# IMU.net
KiCad netlist of a schematic drawn in Altium Designer
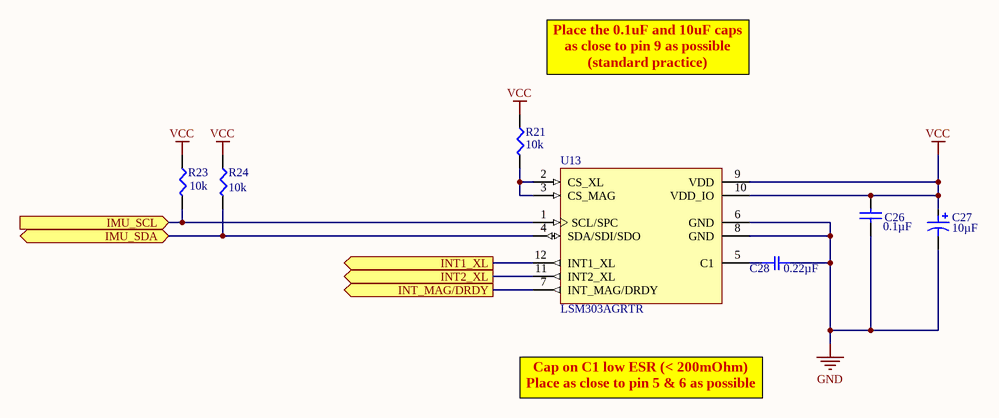
[diagram p0: IMU.SchDoc]

(export (version "E")
  (design (tool "Eeschema 10.0.6"))
  (components
    (comp (ref "C26")
      (value "CL10B104KO8NFNC")
      (footprint "C0603N")
      (fields
        (field (name "HOUSEPART") "NO")
        (field (name "TOLERANCE") "±10%")
        (field (name "VOLTAGE") "16V")
        (field (name "CAPACITANCE") "0.1µF")
      )
      (libsource (lib "MF_Passives") (part "CAPACITOR_NP"))
    )
    (comp (ref "C27")
      (value "10µF")
      (footprint "2917")
      (description "10µF 12.5V Aluminum Polymer Capacitor 2917 (7343 Metric) 60 mOhm 1000 Hrs @ 105°C")
      (fields (field (name "HOUSEPART") "NO") (field (name "MPN") "EEF-CD1B100R"))
      (libsource (lib "Passives") (part "CAPACITOR_P"))
    )
    (comp (ref "C28")
      (value "0.22µF")
      (footprint "SMD-0603C")
      (description "CAP CER 0.22UF 25V X7R 0603")
      (fields
        (field (name "DIGI-KEY PART NUMBER") "490-8017-1-ND")
        (field (name "PART NUMBER") "GCM188R71E224KA55J")
      )
      (libsource (lib "capacitor_murata_0603") (part "GCM188R71E224KA55J"))
    )
    (comp (ref "R21")
      (value "10k")
      (footprint "SMD-0603-RES")
      (description "RES SMD 10K OHM 1% 1/10W 0603")
      (fields
        (field (name "PART NUMBER") "ERJ-3EKF1002V")
        (field (name "DIGI-KEY PART NUMBER") "P10.0KHCT-ND")
      )
      (libsource (lib "Panasonic_ERJ_0603") (part "ERJ-3EKF1002V"))
    )
    (comp (ref "R23")
      (value "10k")
      (footprint "SMD-0603-RES")
      (description "RES SMD 10K OHM 1% 1/10W 0603")
      (fields
        (field (name "PART NUMBER") "ERJ-3EKF1002V")
        (field (name "DIGI-KEY PART NUMBER") "P10.0KHCT-ND")
      )
      (libsource (lib "Panasonic_ERJ_0603") (part "ERJ-3EKF1002V"))
    )
    (comp (ref "R24")
      (value "10k")
      (footprint "SMD-0603-RES")
      (description "RES SMD 10K OHM 1% 1/10W 0603")
      (fields
        (field (name "PART NUMBER") "ERJ-3EKF1002V")
        (field (name "DIGI-KEY PART NUMBER") "P10.0KHCT-ND")
      )
      (libsource (lib "Panasonic_ERJ_0603") (part "ERJ-3EKF1002V"))
    )
    (comp (ref "U13")
      (value "LSM303AGRTR")
      (footprint "LGA12R50P_200X200X100")
      (libsource (lib "LSM303AGRTR") (part "CMP-98f6527696964731-1"))
    )
  )
  (nets
    (net (code "1") (name "/IMU_SCL") (class "Default")
      (node (ref "R23") (pin "2") (pinfunction "2_2") (pintype "passive"))
      (node (ref "U13") (pin "1") (pinfunction "SCL/SPC_1") (pintype "input"))
    )
    (net (code "2") (name "/IMU_SDA") (class "Default")
      (node (ref "R24") (pin "2") (pinfunction "2_2") (pintype "passive"))
      (node (ref "U13") (pin "4") (pinfunction "SDA/SDI/SDO_4") (pintype "bidirectional"))
    )
    (net (code "3") (name "/INT1_XL") (class "Default")
      (node (ref "U13") (pin "12") (pinfunction "INT1_XL_12") (pintype "output"))
    )
    (net (code "4") (name "/INT2_XL") (class "Default")
      (node (ref "U13") (pin "11") (pinfunction "INT2_XL_11") (pintype "output"))
    )
    (net (code "5") (name "/INT_MAG{slash}DRDY") (class "Default")
      (node (ref "U13") (pin "7") (pinfunction "INT_MAG/DRDY_7") (pintype "output"))
    )
    (net (code "6") (name "GND") (class "Default")
      (node (ref "C26") (pin "1") (pinfunction "1_1") (pintype "passive"))
      (node (ref "C27") (pin "2") (pinfunction "2_2") (pintype "passive"))
      (node (ref "C28") (pin "2") (pinfunction "2_2") (pintype "passive"))
      (node (ref "U13") (pin "6") (pinfunction "GND_6") (pintype "power_in"))
      (node (ref "U13") (pin "8") (pinfunction "GND_8") (pintype "power_in"))
    )
    (net (code "7") (name "Net-(U13-C1)") (class "Default")
      (node (ref "C28") (pin "1") (pinfunction "1_1") (pintype "passive"))
      (node (ref "U13") (pin "5") (pinfunction "C1_5") (pintype "passive"))
    )
    (net (code "8") (name "Net-(U13-CS_MAG)") (class "Default")
      (node (ref "R21") (pin "2") (pinfunction "2_2") (pintype "passive"))
      (node (ref "U13") (pin "2") (pinfunction "CS_XL_2") (pintype "input"))
      (node (ref "U13") (pin "3") (pinfunction "CS_MAG_3") (pintype "input"))
    )
    (net (code "9") (name "VCC") (class "Default")
      (node (ref "C26") (pin "2") (pinfunction "2_2") (pintype "passive"))
      (node (ref "C27") (pin "1") (pinfunction "1_1") (pintype "passive"))
      (node (ref "R21") (pin "1") (pinfunction "1_1") (pintype "passive"))
      (node (ref "R23") (pin "1") (pinfunction "1_1") (pintype "passive"))
      (node (ref "R24") (pin "1") (pinfunction "1_1") (pintype "passive"))
      (node (ref "U13") (pin "10") (pinfunction "VDD_IO_10") (pintype "power_in"))
      (node (ref "U13") (pin "9") (pinfunction "VDD_9") (pintype "power_in"))
    )
  )
)
